# 2_interface.net
KiCad netlist of a schematic drawn in Altium Designer
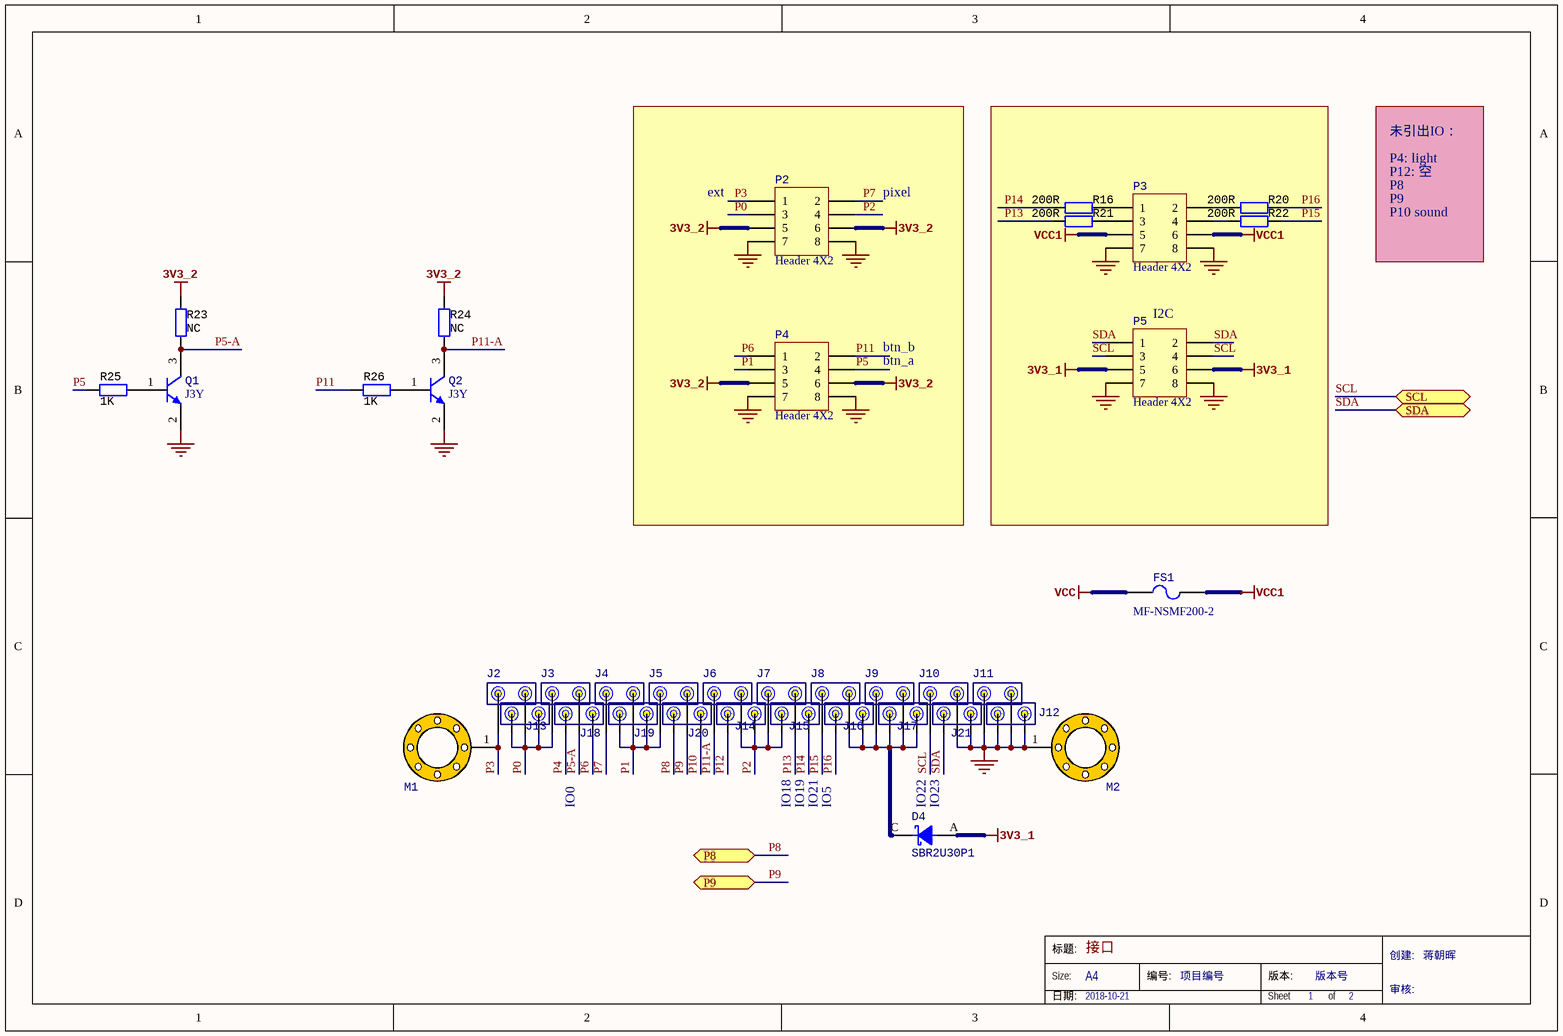
[diagram p0: 2.interface.SchDoc]

(export (version "E")
  (design (tool "Eeschema 10.0.6"))
  (components
    (comp (ref "D4")
      (value "SBR2U30P1")
      (footprint "POWERDI123")
      (fields (field (name "PARTNUMBER") "?") (field (name "PUBLISHER") "Altium Limited"))
      (libsource (lib "03.常用器件") (part "Diode_Schottky"))
    )
    (comp (ref "FS1")
      (value "MF-NSMF200-2")
      (footprint "R1206")
      (description "保险管")
      (libsource (lib "Miscellaneous Devices") (part "电子保险丝"))
    )
    (comp (ref "J2") (value "~") (footprint "顶针座子（2.54MM）") (libsource (lib "Schlib1") (part "pogopin")))
    (comp (ref "J3") (value "~") (footprint "顶针座子（2.54MM）") (libsource (lib "Schlib1") (part "pogopin")))
    (comp (ref "J4") (value "~") (footprint "顶针座子（2.54MM）") (libsource (lib "Schlib1") (part "pogopin")))
    (comp (ref "J5") (value "~") (footprint "顶针座子（2.54MM）") (libsource (lib "Schlib1") (part "pogopin")))
    (comp (ref "J6") (value "~") (footprint "顶针座子（2.54MM）") (libsource (lib "Schlib1") (part "pogopin")))
    (comp (ref "J7") (value "~") (footprint "顶针座子（2.54MM）") (libsource (lib "Schlib1") (part "pogopin")))
    (comp (ref "J8") (value "~") (footprint "顶针座子（2.54MM）") (libsource (lib "Schlib1") (part "pogopin")))
    (comp (ref "J9") (value "~") (footprint "顶针座子（2.54MM）") (libsource (lib "Schlib1") (part "pogopin")))
    (comp (ref "J10") (value "~") (footprint "顶针座子（2.54MM）") (libsource (lib "Schlib1") (part "pogopin")))
    (comp (ref "J11") (value "~") (footprint "顶针座子（2.54MM）") (libsource (lib "Schlib1") (part "pogopin")))
    (comp (ref "J12") (value "~") (footprint "顶针座子（2.54MM）") (libsource (lib "Schlib1") (part "pogopin_32")))
    (comp (ref "J13") (value "~") (footprint "顶针座子（2.54MM）") (libsource (lib "Schlib1") (part "pogopin_32")))
    (comp (ref "J14") (value "~") (footprint "顶针座子（2.54MM）") (libsource (lib "Schlib1") (part "pogopin_32")))
    (comp (ref "J15") (value "~") (footprint "顶针座子（2.54MM）") (libsource (lib "Schlib1") (part "pogopin_32")))
    (comp (ref "J16") (value "~") (footprint "顶针座子（2.54MM）") (libsource (lib "Schlib1") (part "pogopin_32")))
    (comp (ref "J17") (value "~") (footprint "顶针座子（2.54MM）") (libsource (lib "Schlib1") (part "pogopin_32")))
    (comp (ref "J18") (value "~") (footprint "顶针座子（2.54MM）") (libsource (lib "Schlib1") (part "pogopin_32")))
    (comp (ref "J19") (value "~") (footprint "顶针座子（2.54MM）") (libsource (lib "Schlib1") (part "pogopin_32")))
    (comp (ref "J20") (value "~") (footprint "顶针座子（2.54MM）") (libsource (lib "Schlib1") (part "pogopin_32")))
    (comp (ref "J21") (value "~") (footprint "顶针座子（2.54MM）") (libsource (lib "Schlib1") (part "pogopin_32")))
    (comp (ref "M1") (value "~") (footprint "3MM螺丝孔") (libsource (lib "labplus-connector") (part "screw")))
    (comp (ref "M2") (value "~") (footprint "3MM螺丝孔") (libsource (lib "labplus-connector") (part "screw")))
    (comp (ref "P2")
      (value "Header 4X2")
      (footprint "HDR2X4")
      (description "Header, 4-Pin, Dual row")
      (fields (field (name "PUBLISHER") "Altium Limited"))
      (libsource (lib "Miscellaneous Connectors") (part "Header 4X2"))
    )
    (comp (ref "P3")
      (value "Header 4X2")
      (footprint "HDR2X4")
      (description "Header, 4-Pin, Dual row")
      (fields (field (name "PUBLISHER") "Altium Limited"))
      (libsource (lib "Miscellaneous Connectors") (part "Header 4X2"))
    )
    (comp (ref "P4")
      (value "Header 4X2")
      (footprint "HDR2X4")
      (description "Header, 4-Pin, Dual row")
      (fields (field (name "PUBLISHER") "Altium Limited"))
      (libsource (lib "Miscellaneous Connectors") (part "Header 4X2"))
    )
    (comp (ref "P5")
      (value "Header 4X2")
      (footprint "HDR2X4")
      (description "Header, 4-Pin, Dual row")
      (fields (field (name "PUBLISHER") "Altium Limited"))
      (libsource (lib "Miscellaneous Connectors") (part "Header 4X2"))
    )
    (comp (ref "Q1")
      (value "J3Y")
      (footprint "DFN 3L")
      (description "NPN General Purpose Amplifier")
      (fields (field (name "PUBLISHER") "Altium Limited"))
      (libsource (lib "Schlib1") (part "2N3904"))
    )
    (comp (ref "Q2")
      (value "J3Y")
      (footprint "DFN 3L")
      (description "NPN General Purpose Amplifier")
      (fields (field (name "PUBLISHER") "Altium Limited"))
      (libsource (lib "Schlib1") (part "2N3904"))
    )
    (comp (ref "R16")
      (value "200R")
      (footprint "0402")
      (description "RES, 1.0k ohm, 5%, 0.1W, 0603")
      (fields
        (field (name "PARTNUMBER") "RC0603JR-071KL")
        (field (name "MANUFACTURER") "Yageo America")
        (field (name "PUBLISHER") "Texas Instruments")
      )
      (libsource (lib "") (part "RES1_2"))
    )
    (comp (ref "R20")
      (value "200R")
      (footprint "0402")
      (description "RES, 1.0k ohm, 5%, 0.1W, 0603")
      (fields
        (field (name "PARTNUMBER") "RC0603JR-071KL")
        (field (name "MANUFACTURER") "Yageo America")
        (field (name "PUBLISHER") "Texas Instruments")
      )
      (libsource (lib "") (part "RES1_2"))
    )
    (comp (ref "R21")
      (value "200R")
      (footprint "0402")
      (description "RES, 1.0k ohm, 5%, 0.1W, 0603")
      (fields
        (field (name "PARTNUMBER") "RC0603JR-071KL")
        (field (name "MANUFACTURER") "Yageo America")
        (field (name "PUBLISHER") "Texas Instruments")
      )
      (libsource (lib "") (part "RES1_2"))
    )
    (comp (ref "R22")
      (value "200R")
      (footprint "0402")
      (description "RES, 1.0k ohm, 5%, 0.1W, 0603")
      (fields
        (field (name "PARTNUMBER") "RC0603JR-071KL")
        (field (name "MANUFACTURER") "Yageo America")
        (field (name "PUBLISHER") "Texas Instruments")
      )
      (libsource (lib "") (part "RES1_2"))
    )
    (comp (ref "R23")
      (value "NC")
      (footprint "0402")
      (description "RES, 1.0k ohm, 5%, 0.1W, 0603")
      (fields
        (field (name "PARTNUMBER") "RC0603JR-071KL")
        (field (name "MANUFACTURER") "Yageo America")
        (field (name "PUBLISHER") "Texas Instruments")
      )
      (libsource (lib "") (part "RES1_1"))
    )
    (comp (ref "R24")
      (value "NC")
      (footprint "0402")
      (description "RES, 1.0k ohm, 5%, 0.1W, 0603")
      (fields
        (field (name "PARTNUMBER") "RC0603JR-071KL")
        (field (name "MANUFACTURER") "Yageo America")
        (field (name "PUBLISHER") "Texas Instruments")
      )
      (libsource (lib "") (part "RES1_1"))
    )
    (comp (ref "R25")
      (value "1K")
      (footprint "0402")
      (description "RES, 1.0k ohm, 5%, 0.1W, 0603")
      (fields
        (field (name "PARTNUMBER") "RC0603JR-071KL")
        (field (name "MANUFACTURER") "Yageo America")
        (field (name "PUBLISHER") "Texas Instruments")
      )
      (libsource (lib "03.常用器件") (part "RES1"))
    )
    (comp (ref "R26")
      (value "1K")
      (footprint "0402")
      (description "RES, 1.0k ohm, 5%, 0.1W, 0603")
      (fields
        (field (name "PARTNUMBER") "RC0603JR-071KL")
        (field (name "MANUFACTURER") "Yageo America")
        (field (name "PUBLISHER") "Texas Instruments")
      )
      (libsource (lib "03.常用器件") (part "RES1"))
    )
  )
  (nets
    (net (code "1") (name "/P0") (class "Default")
      (node (ref "J13") (pin "1") (pinfunction "1_1") (pintype "passive"))
      (node (ref "J13") (pin "2") (pinfunction "2_2") (pintype "passive"))
      (node (ref "J2") (pin "2") (pinfunction "2_2") (pintype "passive"))
      (node (ref "J3") (pin "1") (pinfunction "1_1") (pintype "passive"))
      (node (ref "P2") (pin "3") (pinfunction "3_3") (pintype "passive"))
    )
    (net (code "2") (name "/P1") (class "Default")
      (node (ref "J19") (pin "1") (pinfunction "1_1") (pintype "passive"))
      (node (ref "J19") (pin "2") (pinfunction "2_2") (pintype "passive"))
      (node (ref "J4") (pin "2") (pinfunction "2_2") (pintype "passive"))
      (node (ref "J5") (pin "1") (pinfunction "1_1") (pintype "passive"))
      (node (ref "P4") (pin "3") (pinfunction "3_3") (pintype "passive"))
    )
    (net (code "3") (name "/P2") (class "Default")
      (node (ref "J14") (pin "2") (pinfunction "2_2") (pintype "passive"))
      (node (ref "J15") (pin "1") (pinfunction "1_1") (pintype "passive"))
      (node (ref "J6") (pin "2") (pinfunction "2_2") (pintype "passive"))
      (node (ref "J7") (pin "1") (pinfunction "1_1") (pintype "passive"))
      (node (ref "P2") (pin "4") (pinfunction "4_4") (pintype "passive"))
    )
    (net (code "4") (name "/P3") (class "Default")
      (node (ref "J2") (pin "1") (pinfunction "1_1") (pintype "passive"))
      (node (ref "M1") (pin "1") (pinfunction "1_1") (pintype "passive"))
      (node (ref "P2") (pin "1") (pinfunction "1_1") (pintype "passive"))
    )
    (net (code "5") (name "/P4") (class "Default")
      (node (ref "J18") (pin "1") (pinfunction "1_1") (pintype "passive"))
    )
    (net (code "6") (name "/P5") (class "Default")
      (node (ref "P4") (pin "4") (pinfunction "4_4") (pintype "passive"))
      (node (ref "R25") (pin "1") (pinfunction "1_1") (pintype "passive"))
    )
    (net (code "7") (name "/P5-A") (class "Default")
      (node (ref "J3") (pin "2") (pinfunction "2_2") (pintype "passive"))
      (node (ref "Q1") (pin "3") (pinfunction "C_3") (pintype "passive"))
      (node (ref "R23") (pin "2") (pinfunction "2_2") (pintype "passive"))
    )
    (net (code "8") (name "/P6") (class "Default")
      (node (ref "J18") (pin "2") (pinfunction "2_2") (pintype "passive"))
      (node (ref "P4") (pin "1") (pinfunction "1_1") (pintype "passive"))
    )
    (net (code "9") (name "/P7") (class "Default")
      (node (ref "J4") (pin "1") (pinfunction "1_1") (pintype "passive"))
      (node (ref "P2") (pin "2") (pinfunction "2_2") (pintype "passive"))
    )
    (net (code "10") (name "/P8") (class "Default")
      (node (ref "J20") (pin "1") (pinfunction "1_1") (pintype "passive"))
    )
    (net (code "11") (name "/P9") (class "Default")
      (node (ref "J5") (pin "2") (pinfunction "2_2") (pintype "passive"))
    )
    (net (code "12") (name "/P10") (class "Default")
      (node (ref "J20") (pin "2") (pinfunction "2_2") (pintype "passive"))
    )
    (net (code "13") (name "/P11") (class "Default")
      (node (ref "P4") (pin "2") (pinfunction "2_2") (pintype "passive"))
      (node (ref "R26") (pin "1") (pinfunction "1_1") (pintype "passive"))
    )
    (net (code "14") (name "/P11-A") (class "Default")
      (node (ref "J6") (pin "1") (pinfunction "1_1") (pintype "passive"))
      (node (ref "Q2") (pin "3") (pinfunction "C_3") (pintype "passive"))
      (node (ref "R24") (pin "2") (pinfunction "2_2") (pintype "passive"))
    )
    (net (code "15") (name "/P12") (class "Default")
      (node (ref "J14") (pin "1") (pinfunction "1_1") (pintype "passive"))
    )
    (net (code "16") (name "/P13") (class "Default")
      (node (ref "J7") (pin "2") (pinfunction "2_2") (pintype "passive"))
      (node (ref "R21") (pin "1") (pinfunction "1_1") (pintype "passive"))
    )
    (net (code "17") (name "/P14") (class "Default")
      (node (ref "J15") (pin "2") (pinfunction "2_2") (pintype "passive"))
      (node (ref "R16") (pin "1") (pinfunction "1_1") (pintype "passive"))
    )
    (net (code "18") (name "/P15") (class "Default")
      (node (ref "J8") (pin "1") (pinfunction "1_1") (pintype "passive"))
      (node (ref "R22") (pin "2") (pinfunction "2_2") (pintype "passive"))
    )
    (net (code "19") (name "/P16") (class "Default")
      (node (ref "J16") (pin "1") (pinfunction "1_1") (pintype "passive"))
      (node (ref "R20") (pin "2") (pinfunction "2_2") (pintype "passive"))
    )
    (net (code "20") (name "/SCL") (class "Default")
      (node (ref "J10") (pin "1") (pinfunction "1_1") (pintype "passive"))
      (node (ref "P5") (pin "3") (pinfunction "3_3") (pintype "passive"))
      (node (ref "P5") (pin "4") (pinfunction "4_4") (pintype "passive"))
    )
    (net (code "21") (name "/SDA") (class "Default")
      (node (ref "J21") (pin "1") (pinfunction "1_1") (pintype "passive"))
      (node (ref "P5") (pin "1") (pinfunction "1_1") (pintype "passive"))
      (node (ref "P5") (pin "2") (pinfunction "2_2") (pintype "passive"))
    )
    (net (code "22") (name "3V3_1") (class "Default")
      (node (ref "D4") (pin "A") (pinfunction "ANODE_A") (pintype "passive"))
      (node (ref "P5") (pin "5") (pinfunction "5_5") (pintype "passive"))
      (node (ref "P5") (pin "6") (pinfunction "6_6") (pintype "passive"))
    )
    (net (code "23") (name "3V3_2") (class "Default")
      (node (ref "P2") (pin "5") (pinfunction "5_5") (pintype "passive"))
      (node (ref "P2") (pin "6") (pinfunction "6_6") (pintype "passive"))
      (node (ref "P4") (pin "5") (pinfunction "5_5") (pintype "passive"))
      (node (ref "P4") (pin "6") (pinfunction "6_6") (pintype "passive"))
      (node (ref "R23") (pin "1") (pinfunction "1_1") (pintype "passive"))
      (node (ref "R24") (pin "1") (pinfunction "1_1") (pintype "passive"))
    )
    (net (code "24") (name "<NO NET>") (class "Default")
      (node (ref "J10") (pin "2") (pinfunction "2_2") (pintype "passive"))
      (node (ref "J11") (pin "1") (pinfunction "1_1") (pintype "passive"))
      (node (ref "J11") (pin "2") (pinfunction "2_2") (pintype "passive"))
      (node (ref "J12") (pin "1") (pinfunction "1_1") (pintype "passive"))
      (node (ref "J12") (pin "2") (pinfunction "2_2") (pintype "passive"))
      (node (ref "J21") (pin "2") (pinfunction "2_2") (pintype "passive"))
      (node (ref "M2") (pin "1") (pinfunction "1_1") (pintype "passive"))
      (node (ref "P2") (pin "7") (pinfunction "7_7") (pintype "passive"))
      (node (ref "P2") (pin "8") (pinfunction "8_8") (pintype "passive"))
      (node (ref "P3") (pin "7") (pinfunction "7_7") (pintype "passive"))
      (node (ref "P3") (pin "8") (pinfunction "8_8") (pintype "passive"))
      (node (ref "P4") (pin "7") (pinfunction "7_7") (pintype "passive"))
      (node (ref "P4") (pin "8") (pinfunction "8_8") (pintype "passive"))
      (node (ref "P5") (pin "7") (pinfunction "7_7") (pintype "passive"))
      (node (ref "P5") (pin "8") (pinfunction "8_8") (pintype "passive"))
      (node (ref "Q1") (pin "2") (pinfunction "E_2") (pintype "passive"))
      (node (ref "Q2") (pin "2") (pinfunction "E_2") (pintype "passive"))
    )
    (net (code "25") (name "Net-(D4-CATHODE)") (class "Default")
      (node (ref "D4") (pin "C") (pinfunction "CATHODE_C") (pintype "passive"))
      (node (ref "J16") (pin "2") (pinfunction "2_2") (pintype "passive"))
      (node (ref "J17") (pin "1") (pinfunction "1_1") (pintype "passive"))
      (node (ref "J17") (pin "2") (pinfunction "2_2") (pintype "passive"))
      (node (ref "J8") (pin "2") (pinfunction "2_2") (pintype "passive"))
      (node (ref "J9") (pin "1") (pinfunction "1_1") (pintype "passive"))
      (node (ref "J9") (pin "2") (pinfunction "2_2") (pintype "passive"))
    )
    (net (code "26") (name "Net-(P3-Pad1)") (class "Default")
      (node (ref "P3") (pin "1") (pinfunction "1_1") (pintype "passive"))
      (node (ref "R16") (pin "2") (pinfunction "2_2") (pintype "passive"))
    )
    (net (code "27") (name "Net-(P3-Pad2)") (class "Default")
      (node (ref "P3") (pin "2") (pinfunction "2_2") (pintype "passive"))
      (node (ref "R20") (pin "1") (pinfunction "1_1") (pintype "passive"))
    )
    (net (code "28") (name "Net-(P3-Pad3)") (class "Default")
      (node (ref "P3") (pin "3") (pinfunction "3_3") (pintype "passive"))
      (node (ref "R21") (pin "2") (pinfunction "2_2") (pintype "passive"))
    )
    (net (code "29") (name "Net-(P3-Pad4)") (class "Default")
      (node (ref "P3") (pin "4") (pinfunction "4_4") (pintype "passive"))
      (node (ref "R22") (pin "1") (pinfunction "1_1") (pintype "passive"))
    )
    (net (code "30") (name "Net-(Q1-B)") (class "Default")
      (node (ref "Q1") (pin "1") (pinfunction "B_1") (pintype "passive"))
      (node (ref "R25") (pin "2") (pinfunction "2_2") (pintype "passive"))
    )
    (net (code "31") (name "Net-(Q2-B)") (class "Default")
      (node (ref "Q2") (pin "1") (pinfunction "B_1") (pintype "passive"))
      (node (ref "R26") (pin "2") (pinfunction "2_2") (pintype "passive"))
    )
    (net (code "32") (name "VCC") (class "Default")
      (node (ref "FS1") (pin "2") (pinfunction "1_2") (pintype "passive"))
    )
    (net (code "33") (name "VCC1") (class "Default")
      (node (ref "FS1") (pin "1") (pinfunction "0_1") (pintype "passive"))
      (node (ref "P3") (pin "5") (pinfunction "5_5") (pintype "passive"))
      (node (ref "P3") (pin "6") (pinfunction "6_6") (pintype "passive"))
    )
  )
)
